# Sch_Dr_IMU.net
KiCad netlist of a schematic drawn in Altium Designer
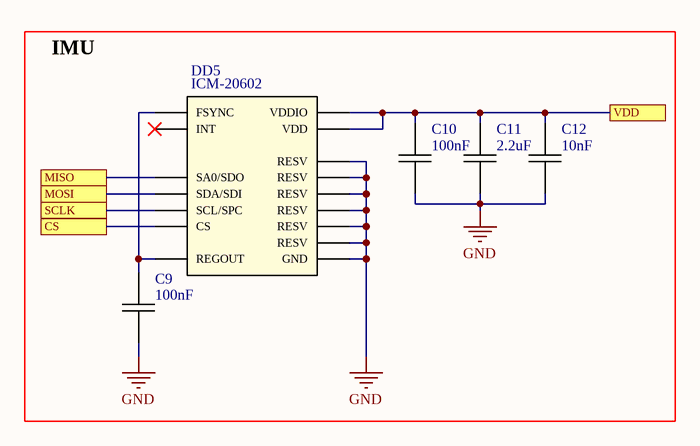
[diagram p0: Sch_Dr_IMU .SchDoc]

(export (version "E")
  (design (tool "Eeschema 10.0.6"))
  (components
    (comp (ref "C9")
      (value "100nF")
      (footprint "Cap_0603")
      (description "CC0603JRX7R8BB104")
      (libsource (lib "Dr_lib") (part "Cap_"))
    )
    (comp (ref "C10")
      (value "100nF")
      (footprint "Cap_0603")
      (description "CC0603JRX7R8BB104")
      (libsource (lib "Dr_lib") (part "Cap_"))
    )
    (comp (ref "C11")
      (value "2.2uF")
      (footprint "Cap_0603")
      (description "CC0603KRX5R7BB225")
      (libsource (lib "Dr_lib") (part "Cap_"))
    )
    (comp (ref "C12")
      (value "10nF")
      (footprint "Cap_0603")
      (description "CC0603JRNPO9BN103")
      (libsource (lib "Dr_lib") (part "Cap_"))
    )
    (comp (ref "DD5")
      (value "ICM-20602")
      (footprint "16-pin LGA")
      (description "6-axis MotionTracking device.\r\n3-axis gyroscope, 3-axis accelerometer")
      (libsource (lib "Dr_lib") (part "ICM-20602"))
    )
  )
  (nets
    (net (code "1") (name "/CS") (class "Default")
      (node (ref "DD5") (pin "5") (pinfunction "CS_5") (pintype "passive"))
    )
    (net (code "2") (name "/MISO") (class "Default")
      (node (ref "DD5") (pin "4") (pinfunction "SA0/SDO_4") (pintype "passive"))
    )
    (net (code "3") (name "/MOSI") (class "Default")
      (node (ref "DD5") (pin "3") (pinfunction "SDA/SDI_3") (pintype "passive"))
    )
    (net (code "4") (name "/SCLK") (class "Default")
      (node (ref "DD5") (pin "2") (pinfunction "SCL/SPC_2") (pintype "passive"))
    )
    (net (code "5") (name "/VDD") (class "Default")
      (node (ref "C10") (pin "1") (pinfunction "1_1") (pintype "passive"))
      (node (ref "C11") (pin "1") (pinfunction "1_1") (pintype "passive"))
      (node (ref "C12") (pin "1") (pinfunction "1_1") (pintype "passive"))
      (node (ref "DD5") (pin "1") (pinfunction "VDDIO_1") (pintype "passive"))
      (node (ref "DD5") (pin "16") (pinfunction "VDD_16") (pintype "passive"))
    )
    (net (code "6") (name "GND") (class "Default")
      (node (ref "C10") (pin "2") (pinfunction "2_2") (pintype "passive"))
      (node (ref "C11") (pin "2") (pinfunction "2_2") (pintype "passive"))
      (node (ref "C12") (pin "2") (pinfunction "2_2") (pintype "passive"))
      (node (ref "C9") (pin "2") (pinfunction "2_2") (pintype "passive"))
      (node (ref "DD5") (pin "10") (pinfunction "RESV_10") (pintype "passive"))
      (node (ref "DD5") (pin "11") (pinfunction "RESV_11") (pintype "passive"))
      (node (ref "DD5") (pin "12") (pinfunction "RESV_12") (pintype "passive"))
      (node (ref "DD5") (pin "13") (pinfunction "GND_13") (pintype "passive"))
      (node (ref "DD5") (pin "15") (pinfunction "RESV_15") (pintype "passive"))
      (node (ref "DD5") (pin "7") (pinfunction "RESV_7") (pintype "passive"))
      (node (ref "DD5") (pin "9") (pinfunction "RESV_9") (pintype "passive"))
    )
    (net (code "7") (name "Net-(DD5-FSYNC)") (class "Default")
      (node (ref "C9") (pin "1") (pinfunction "1_1") (pintype "passive"))
      (node (ref "DD5") (pin "14") (pinfunction "REGOUT_14") (pintype "passive"))
      (node (ref "DD5") (pin "8") (pinfunction "FSYNC_8") (pintype "passive"))
    )
    (net (code "8") (name "unconnected-(DD5-INT-Pad6)") (class "Default")
      (node (ref "DD5") (pin "6") (pinfunction "INT_6") (pintype "passive+no_connect"))
    )
  )
)
